# 1_PMIC_1.net
KiCad netlist of a schematic drawn in Altium Designer
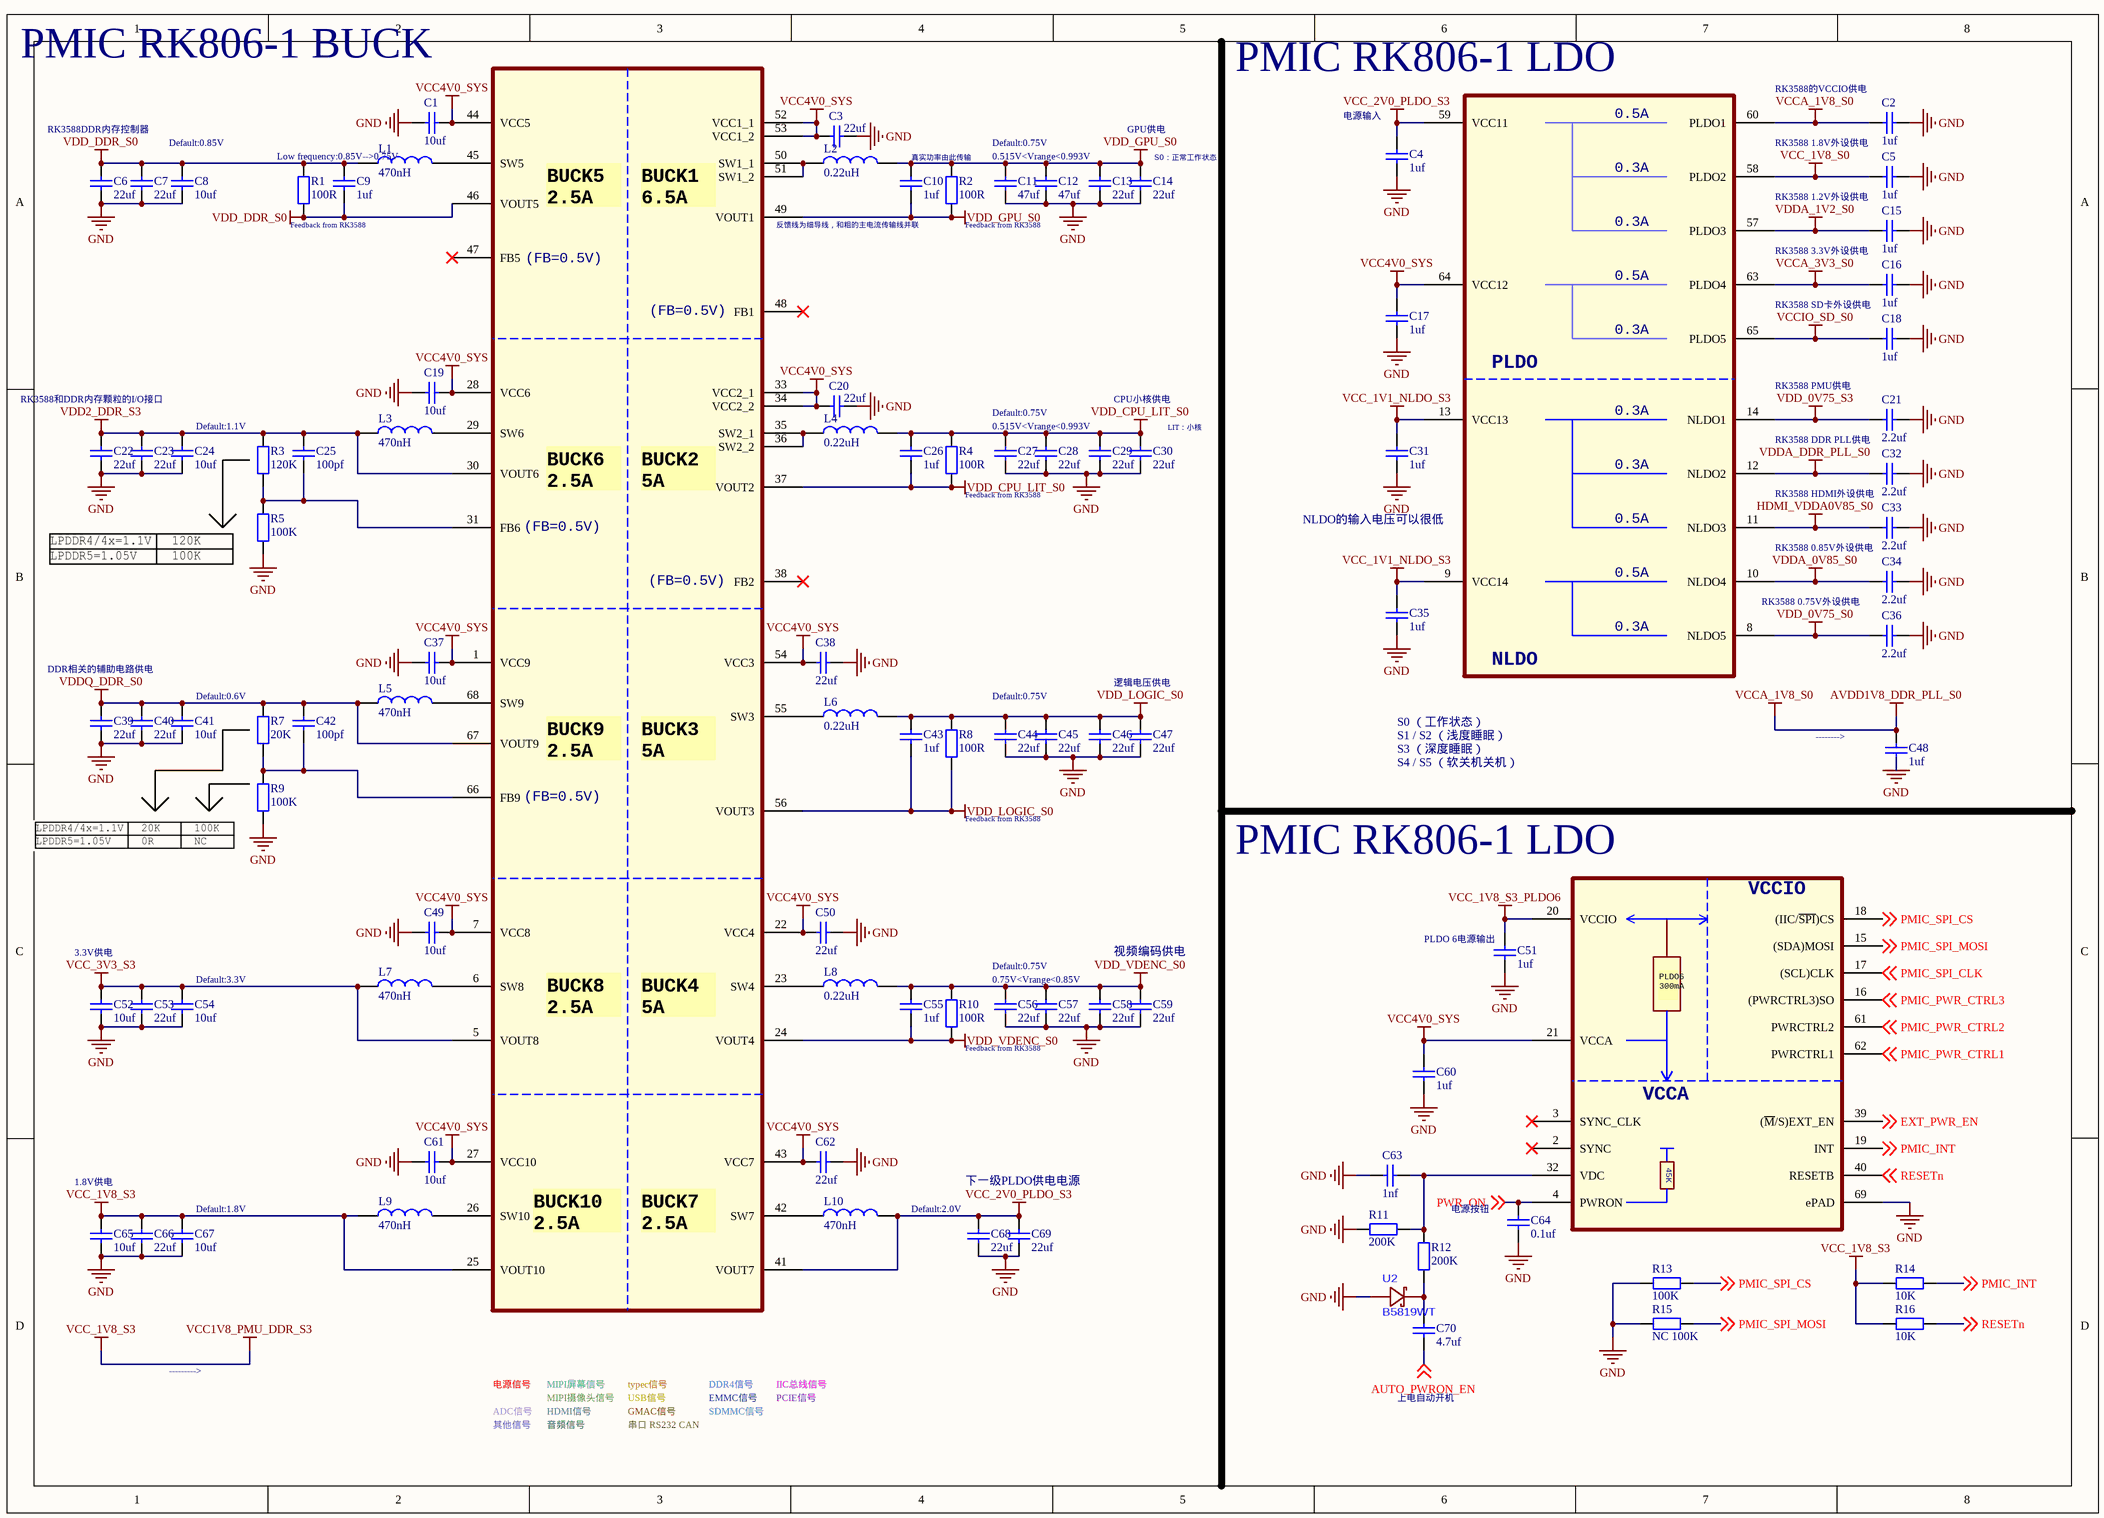
[diagram p0: 1.PMIC_1.SchDoc]

(export (version "E")
  (design (tool "Eeschema 10.0.6"))
  (components
    (comp (ref "C1")
      (value "10uf")
      (footprint "0.PCB1:C0603_L")
      (description "贴片电容/MLCC电容")
      (libsource (lib "RK3588") (part "C"))
    )
    (comp (ref "C2")
      (value "1uf")
      (footprint "0.PCB1:C0402_L")
      (description "贴片电容/MLCC电容")
      (libsource (lib "RK3588") (part "C"))
    )
    (comp (ref "C3")
      (value "22uf")
      (footprint "0.PCB1:C0603_L")
      (description "贴片电容/MLCC电容")
      (libsource (lib "RK3588") (part "C"))
    )
    (comp (ref "C4")
      (value "1uf")
      (footprint "0.PCB1:C0402_L")
      (description "贴片电容/MLCC电容")
      (libsource (lib "RK3588") (part "C"))
    )
    (comp (ref "C5")
      (value "1uf")
      (footprint "0.PCB1:C0402_L")
      (description "贴片电容/MLCC电容")
      (libsource (lib "RK3588") (part "C"))
    )
    (comp (ref "C6")
      (value "22uf")
      (footprint "0.PCB1:C0603_L")
      (description "贴片电容/MLCC电容")
      (libsource (lib "RK3588") (part "C"))
    )
    (comp (ref "C7")
      (value "22uf")
      (footprint "0.PCB1:C0603_L")
      (description "贴片电容/MLCC电容")
      (libsource (lib "RK3588") (part "C"))
    )
    (comp (ref "C8")
      (value "10uf")
      (footprint "0.PCB1:C0402_L")
      (description "贴片电容/MLCC电容")
      (libsource (lib "RK3588") (part "C"))
    )
    (comp (ref "C9")
      (value "1uf")
      (footprint "0.PCB1:C0402_L")
      (description "贴片电容/MLCC电容")
      (libsource (lib "RK3588") (part "C"))
    )
    (comp (ref "C10")
      (value "1uf")
      (footprint "0.PCB1:C0402_L")
      (description "贴片电容/MLCC电容")
      (libsource (lib "RK3588") (part "C"))
    )
    (comp (ref "C11")
      (value "47uf")
      (footprint "0.PCB1:C0805_L")
      (description "贴片电容/MLCC电容")
      (libsource (lib "RK3588") (part "C"))
    )
    (comp (ref "C12")
      (value "47uf")
      (footprint "0.PCB1:C0805_L")
      (description "贴片电容/MLCC电容")
      (libsource (lib "RK3588") (part "C"))
    )
    (comp (ref "C13")
      (value "22uf")
      (footprint "0.PCB1:C0603_L")
      (description "贴片电容/MLCC电容")
      (libsource (lib "RK3588") (part "C"))
    )
    (comp (ref "C14")
      (value "22uf")
      (footprint "0.PCB1:C0603_L")
      (description "贴片电容/MLCC电容")
      (libsource (lib "RK3588") (part "C"))
    )
    (comp (ref "C15")
      (value "1uf")
      (footprint "0.PCB1:C0402_L")
      (description "贴片电容/MLCC电容")
      (libsource (lib "RK3588") (part "C"))
    )
    (comp (ref "C16")
      (value "1uf")
      (footprint "0.PCB1:C0402_L")
      (description "贴片电容/MLCC电容")
      (libsource (lib "RK3588") (part "C"))
    )
    (comp (ref "C17")
      (value "1uf")
      (footprint "0.PCB1:C0402_L")
      (description "贴片电容/MLCC电容")
      (libsource (lib "RK3588") (part "C"))
    )
    (comp (ref "C18")
      (value "1uf")
      (footprint "0.PCB1:C0402_L")
      (description "贴片电容/MLCC电容")
      (libsource (lib "RK3588") (part "C"))
    )
    (comp (ref "C19")
      (value "10uf")
      (footprint "0.PCB1:C0603_L")
      (description "贴片电容/MLCC电容")
      (libsource (lib "RK3588") (part "C"))
    )
    (comp (ref "C20")
      (value "22uf")
      (footprint "0.PCB1:C0603_L")
      (description "贴片电容/MLCC电容")
      (libsource (lib "RK3588") (part "C"))
    )
    (comp (ref "C21")
      (value "2.2uf")
      (footprint "0.PCB1:C0402_L")
      (description "贴片电容/MLCC电容")
      (libsource (lib "RK3588") (part "C"))
    )
    (comp (ref "C22")
      (value "22uf")
      (footprint "0.PCB1:C0603_L")
      (description "贴片电容/MLCC电容")
      (libsource (lib "RK3588") (part "C"))
    )
    (comp (ref "C23")
      (value "22uf")
      (footprint "0.PCB1:C0603_L")
      (description "贴片电容/MLCC电容")
      (libsource (lib "RK3588") (part "C"))
    )
    (comp (ref "C24")
      (value "10uf")
      (footprint "0.PCB1:C0402_L")
      (description "贴片电容/MLCC电容")
      (libsource (lib "RK3588") (part "C"))
    )
    (comp (ref "C25")
      (value "100pf")
      (footprint "0.PCB1:C0402_L")
      (description "贴片电容/MLCC电容")
      (libsource (lib "RK3588") (part "C"))
    )
    (comp (ref "C26")
      (value "1uf")
      (footprint "0.PCB1:C0402_L")
      (description "贴片电容/MLCC电容")
      (libsource (lib "RK3588") (part "C"))
    )
    (comp (ref "C27")
      (value "22uf")
      (footprint "0.PCB1:C0603_L")
      (description "贴片电容/MLCC电容")
      (libsource (lib "RK3588") (part "C"))
    )
    (comp (ref "C28")
      (value "22uf")
      (footprint "0.PCB1:C0603_L")
      (description "贴片电容/MLCC电容")
      (libsource (lib "RK3588") (part "C"))
    )
    (comp (ref "C29")
      (value "22uf")
      (footprint "0.PCB1:C0603_L")
      (description "贴片电容/MLCC电容")
      (libsource (lib "RK3588") (part "C"))
    )
    (comp (ref "C30")
      (value "22uf")
      (footprint "0.PCB1:C0603_L")
      (description "贴片电容/MLCC电容")
      (libsource (lib "RK3588") (part "C"))
    )
    (comp (ref "C31")
      (value "1uf")
      (footprint "0.PCB1:C0402_L")
      (description "贴片电容/MLCC电容")
      (libsource (lib "RK3588") (part "C"))
    )
    (comp (ref "C32")
      (value "2.2uf")
      (footprint "0.PCB1:C0402_L")
      (description "贴片电容/MLCC电容")
      (libsource (lib "RK3588") (part "C"))
    )
    (comp (ref "C33")
      (value "2.2uf")
      (footprint "0.PCB1:C0402_L")
      (description "贴片电容/MLCC电容")
      (libsource (lib "RK3588") (part "C"))
    )
    (comp (ref "C34")
      (value "2.2uf")
      (footprint "0.PCB1:C0402_L")
      (description "贴片电容/MLCC电容")
      (libsource (lib "RK3588") (part "C"))
    )
    (comp (ref "C35")
      (value "1uf")
      (footprint "0.PCB1:C0402_L")
      (description "贴片电容/MLCC电容")
      (libsource (lib "RK3588") (part "C"))
    )
    (comp (ref "C36")
      (value "2.2uf")
      (footprint "0.PCB1:C0402_L")
      (description "贴片电容/MLCC电容")
      (libsource (lib "RK3588") (part "C"))
    )
    (comp (ref "C37")
      (value "10uf")
      (footprint "0.PCB1:C0603_L")
      (description "贴片电容/MLCC电容")
      (libsource (lib "RK3588") (part "C"))
    )
    (comp (ref "C38")
      (value "22uf")
      (footprint "0.PCB1:C0603_L")
      (description "贴片电容/MLCC电容")
      (libsource (lib "RK3588") (part "C"))
    )
    (comp (ref "C39")
      (value "22uf")
      (footprint "0.PCB1:C0603_L")
      (description "贴片电容/MLCC电容")
      (libsource (lib "RK3588") (part "C"))
    )
    (comp (ref "C40")
      (value "22uf")
      (footprint "0.PCB1:C0603_L")
      (description "贴片电容/MLCC电容")
      (libsource (lib "RK3588") (part "C"))
    )
    (comp (ref "C41")
      (value "10uf")
      (footprint "0.PCB1:C0402_L")
      (description "贴片电容/MLCC电容")
      (libsource (lib "RK3588") (part "C"))
    )
    (comp (ref "C42")
      (value "100pf")
      (footprint "0.PCB1:C0402_L")
      (description "贴片电容/MLCC电容")
      (libsource (lib "RK3588") (part "C"))
    )
    (comp (ref "C43")
      (value "1uf")
      (footprint "0.PCB1:C0402_L")
      (description "贴片电容/MLCC电容")
      (libsource (lib "RK3588") (part "C"))
    )
    (comp (ref "C44")
      (value "22uf")
      (footprint "0.PCB1:C0805_L")
      (description "贴片电容/MLCC电容")
      (libsource (lib "RK3588") (part "C"))
    )
    (comp (ref "C45")
      (value "22uf")
      (footprint "0.PCB1:C0805_L")
      (description "贴片电容/MLCC电容")
      (libsource (lib "RK3588") (part "C"))
    )
    (comp (ref "C46")
      (value "22uf")
      (footprint "0.PCB1:C0603_L")
      (description "贴片电容/MLCC电容")
      (libsource (lib "RK3588") (part "C"))
    )
    (comp (ref "C47")
      (value "22uf")
      (footprint "0.PCB1:C0603_L")
      (description "贴片电容/MLCC电容")
      (libsource (lib "RK3588") (part "C"))
    )
    (comp (ref "C48")
      (value "1uf")
      (footprint "0.PCB1:C0402_L")
      (description "贴片电容/MLCC电容")
      (libsource (lib "RK3588") (part "C"))
    )
    (comp (ref "C49")
      (value "10uf")
      (footprint "0.PCB1:C0603_L")
      (description "贴片电容/MLCC电容")
      (libsource (lib "RK3588") (part "C"))
    )
    (comp (ref "C50")
      (value "22uf")
      (footprint "0.PCB1:C0603_L")
      (description "贴片电容/MLCC电容")
      (libsource (lib "RK3588") (part "C"))
    )
    (comp (ref "C51")
      (value "1uf")
      (footprint "0.PCB1:C0402_L")
      (description "贴片电容/MLCC电容")
      (libsource (lib "RK3588") (part "C"))
    )
    (comp (ref "C52")
      (value "10uf")
      (footprint "0.PCB1:C0603_L")
      (description "贴片电容/MLCC电容")
      (libsource (lib "RK3588") (part "C"))
    )
    (comp (ref "C53")
      (value "22uf")
      (footprint "0.PCB1:C0603_L")
      (description "贴片电容/MLCC电容")
      (libsource (lib "RK3588") (part "C"))
    )
    (comp (ref "C54")
      (value "10uf")
      (footprint "0.PCB1:C0402_L")
      (description "贴片电容/MLCC电容")
      (libsource (lib "RK3588") (part "C"))
    )
    (comp (ref "C55")
      (value "1uf")
      (footprint "0.PCB1:C0402_L")
      (description "贴片电容/MLCC电容")
      (libsource (lib "RK3588") (part "C"))
    )
    (comp (ref "C56")
      (value "22uf")
      (footprint "0.PCB1:C0805_L")
      (description "贴片电容/MLCC电容")
      (libsource (lib "RK3588") (part "C"))
    )
    (comp (ref "C57")
      (value "22uf")
      (footprint "0.PCB1:C0805_L")
      (description "贴片电容/MLCC电容")
      (libsource (lib "RK3588") (part "C"))
    )
    (comp (ref "C58")
      (value "22uf")
      (footprint "0.PCB1:C0603_L")
      (description "贴片电容/MLCC电容")
      (libsource (lib "RK3588") (part "C"))
    )
    (comp (ref "C59")
      (value "22uf")
      (footprint "0.PCB1:C0603_L")
      (description "贴片电容/MLCC电容")
      (libsource (lib "RK3588") (part "C"))
    )
    (comp (ref "C60")
      (value "1uf")
      (footprint "0.PCB1:C0402_L")
      (description "贴片电容/MLCC电容")
      (libsource (lib "RK3588") (part "C"))
    )
    (comp (ref "C61")
      (value "10uf")
      (footprint "0.PCB1:C0603_L")
      (description "贴片电容/MLCC电容")
      (libsource (lib "RK3588") (part "C"))
    )
    (comp (ref "C62")
      (value "22uf")
      (footprint "0.PCB1:C0603_L")
      (description "贴片电容/MLCC电容")
      (libsource (lib "RK3588") (part "C"))
    )
    (comp (ref "C63")
      (value "1nf")
      (footprint "0.PCB1:C0402_L")
      (description "贴片电容/MLCC电容")
      (libsource (lib "RK3588") (part "C"))
    )
    (comp (ref "C64")
      (value "0.1uf")
      (footprint "0.PCB1:C0402_L")
      (description "贴片电容/MLCC电容")
      (libsource (lib "RK3588") (part "C"))
    )
    (comp (ref "C65")
      (value "10uf")
      (footprint "0.PCB1:C0603_L")
      (description "贴片电容/MLCC电容")
      (libsource (lib "RK3588") (part "C"))
    )
    (comp (ref "C66")
      (value "22uf")
      (footprint "0.PCB1:C0603_L")
      (description "贴片电容/MLCC电容")
      (libsource (lib "RK3588") (part "C"))
    )
    (comp (ref "C67")
      (value "10uf")
      (footprint "0.PCB1:C0402_L")
      (description "贴片电容/MLCC电容")
      (libsource (lib "RK3588") (part "C"))
    )
    (comp (ref "C68")
      (value "22uf")
      (footprint "0.PCB1:C0603_L")
      (description "贴片电容/MLCC电容")
      (libsource (lib "RK3588") (part "C"))
    )
    (comp (ref "C69")
      (value "22uf")
      (footprint "0.PCB1:C0603_L")
      (description "贴片电容/MLCC电容")
      (libsource (lib "RK3588") (part "C"))
    )
    (comp (ref "C70")
      (value "4.7uf")
      (footprint "0.PCB1:C0402_L")
      (description "贴片电容/MLCC电容")
      (libsource (lib "RK3588") (part "C"))
    )
    (comp (ref "L1")
      (value "470nH")
      (footprint "0.PCB1:L0805")
      (description "贴片小功率电感")
      (libsource (lib "RK3588") (part "L"))
    )
    (comp (ref "L2")
      (value "0.22uH")
      (footprint "0.PCB1:L0805")
      (description "贴片小功率电感")
      (libsource (lib "") (part "L_1"))
    )
    (comp (ref "L3")
      (value "470nH")
      (footprint "0.PCB1:L0805")
      (description "贴片小功率电感")
      (libsource (lib "RK3588") (part "L"))
    )
    (comp (ref "L4")
      (value "0.22uH")
      (footprint "0.PCB1:L0805")
      (description "贴片小功率电感")
      (libsource (lib "") (part "L_1"))
    )
    (comp (ref "L5")
      (value "470nH")
      (footprint "0.PCB1:L0805")
      (description "贴片小功率电感")
      (libsource (lib "RK3588") (part "L"))
    )
    (comp (ref "L6")
      (value "0.22uH")
      (footprint "0.PCB1:L0805")
      (description "贴片小功率电感")
      (libsource (lib "") (part "L_1"))
    )
    (comp (ref "L7")
      (value "470nH")
      (footprint "0.PCB1:L0805")
      (description "贴片小功率电感")
      (libsource (lib "RK3588") (part "L"))
    )
    (comp (ref "L8")
      (value "0.22uH")
      (footprint "0.PCB1:L0805")
      (description "贴片小功率电感")
      (libsource (lib "") (part "L_1"))
    )
    (comp (ref "L9")
      (value "470nH")
      (footprint "0.PCB1:L0805")
      (description "贴片小功率电感")
      (libsource (lib "RK3588") (part "L"))
    )
    (comp (ref "L10")
      (value "470nH")
      (footprint "0.PCB1:L0805")
      (description "贴片小功率电感")
      (libsource (lib "") (part "L_1"))
    )
    (comp (ref "R1")
      (value "100R")
      (footprint "0.PCB1:R0402_L")
      (description "贴片电阻")
      (libsource (lib "RK3588") (part "R"))
    )
    (comp (ref "R2")
      (value "100R")
      (footprint "0.PCB1:R0402_L")
      (description "贴片电阻")
      (libsource (lib "RK3588") (part "R"))
    )
    (comp (ref "R3")
      (value "120K")
      (footprint "0.PCB1:R0402_L")
      (description "贴片电阻")
      (libsource (lib "RK3588") (part "R"))
    )
    (comp (ref "R4")
      (value "100R")
      (footprint "0.PCB1:R0402_L")
      (description "贴片电阻")
      (libsource (lib "RK3588") (part "R"))
    )
    (comp (ref "R5")
      (value "100K")
      (footprint "0.PCB1:R0402_L")
      (description "贴片电阻")
      (libsource (lib "RK3588") (part "R"))
    )
    (comp (ref "R7")
      (value "20K")
      (footprint "0.PCB1:R0402_L")
      (description "贴片电阻")
      (libsource (lib "RK3588") (part "R"))
    )
    (comp (ref "R8")
      (value "100R")
      (footprint "0.PCB1:R0402_L")
      (description "贴片电阻")
      (libsource (lib "RK3588") (part "R"))
    )
    (comp (ref "R9")
      (value "100K")
      (footprint "0.PCB1:R0402_L")
      (description "贴片电阻")
      (libsource (lib "RK3588") (part "R"))
    )
    (comp (ref "R10")
      (value "100R")
      (footprint "0.PCB1:R0402_L")
      (description "贴片电阻")
      (libsource (lib "RK3588") (part "R"))
    )
    (comp (ref "R11")
      (value "200K")
      (footprint "0.PCB1:R0402_L")
      (description "贴片电阻")
      (libsource (lib "RK3588") (part "R"))
    )
    (comp (ref "R12")
      (value "200K")
      (footprint "0.PCB1:R0402_L")
      (description "贴片电阻")
      (libsource (lib "RK3588") (part "R"))
    )
    (comp (ref "R13")
      (value "100K")
      (footprint "0.PCB1:R0402_L")
      (description "贴片电阻")
      (libsource (lib "RK3588") (part "R"))
    )
    (comp (ref "R14")
      (value "10K")
      (footprint "0.PCB1:R0402_L")
      (description "贴片电阻")
      (libsource (lib "RK3588") (part "R"))
    )
    (comp (ref "R15")
      (value "NC 100K")
      (footprint "0.PCB1:R0402_L")
      (description "贴片电阻")
      (libsource (lib "RK3588") (part "R"))
    )
    (comp (ref "R16")
      (value "10K")
      (footprint "0.PCB1:R0402_L")
      (description "贴片电阻")
      (libsource (lib "RK3588") (part "R"))
    )
    (comp (ref "U1")
      (value "PMIC_RK806")
      (footprint "0.PCB1:QFN68_7R00X7R00X0R80_T")
      (libsource (lib "RK3588") (part "PMIC_RK806"))
    )
    (comp (ref "U2")
      (value "B5819WT")
      (footprint "0.PCB1:SOD-523_L1.2-W0.8-LS1.6-RD")
      (libsource (lib "RK3588") (part "B5819WT"))
    )
  )
  (nets
    (net (code "1") (name "AUTO_PWRON_EN") (class "Default")
      (node (ref "C70") (pin "2") (pinfunction "2_2") (pintype "passive"))
    )
    (net (code "2") (name "AVDD1V8_DDR_PLL_S0") (class "Default")
      (node (ref "C2") (pin "2") (pinfunction "2_2") (pintype "passive"))
      (node (ref "C48") (pin "1") (pinfunction "1_1") (pintype "passive"))
      (node (ref "U1") (pin "60") (pinfunction "PLDO1_60") (pintype "passive"))
    )
    (net (code "3") (name "EXT_PWR_EN") (class "Default")
      (node (ref "U1") (pin "39") (pinfunction "(~{M}/S)EXT_EN_39") (pintype "passive"))
    )
    (net (code "4") (name "GND") (class "Default")
      (node (ref "C1") (pin "2") (pinfunction "2_2") (pintype "passive"))
      (node (ref "C11") (pin "1") (pinfunction "1_1") (pintype "passive"))
      (node (ref "C12") (pin "1") (pinfunction "1_1") (pintype "passive"))
      (node (ref "C13") (pin "1") (pinfunction "1_1") (pintype "passive"))
      (node (ref "C14") (pin "1") (pinfunction "1_1") (pintype "passive"))
      (node (ref "C15") (pin "1") (pinfunction "1_1") (pintype "passive"))
      (node (ref "C16") (pin "1") (pinfunction "1_1") (pintype "passive"))
      (node (ref "C17") (pin "1") (pinfunction "1_1") (pintype "passive"))
      (node (ref "C18") (pin "1") (pinfunction "1_1") (pintype "passive"))
      (node (ref "C19") (pin "2") (pinfunction "2_2") (pintype "passive"))
      (node (ref "C2") (pin "1") (pinfunction "1_1") (pintype "passive"))
      (node (ref "C20") (pin "2") (pinfunction "2_2") (pintype "passive"))
      (node (ref "C21") (pin "1") (pinfunction "1_1") (pintype "passive"))
      (node (ref "C22") (pin "1") (pinfunction "1_1") (pintype "passive"))
      (node (ref "C23") (pin "1") (pinfunction "1_1") (pintype "passive"))
      (node (ref "C24") (pin "1") (pinfunction "1_1") (pintype "passive"))
      (node (ref "C27") (pin "1") (pinfunction "1_1") (pintype "passive"))
      (node (ref "C28") (pin "1") (pinfunction "1_1") (pintype "passive"))
      (node (ref "C29") (pin "1") (pinfunction "1_1") (pintype "passive"))
      (node (ref "C3") (pin "2") (pinfunction "2_2") (pintype "passive"))
      (node (ref "C30") (pin "1") (pinfunction "1_1") (pintype "passive"))
      (node (ref "C31") (pin "1") (pinfunction "1_1") (pintype "passive"))
      (node (ref "C32") (pin "1") (pinfunction "1_1") (pintype "passive"))
      (node (ref "C33") (pin "1") (pinfunction "1_1") (pintype "passive"))
      (node (ref "C34") (pin "1") (pinfunction "1_1") (pintype "passive"))
      (node (ref "C35") (pin "1") (pinfunction "1_1") (pintype "passive"))
      (node (ref "C36") (pin "1") (pinfunction "1_1") (pintype "passive"))
      (node (ref "C37") (pin "2") (pinfunction "2_2") (pintype "passive"))
      (node (ref "C38") (pin "2") (pinfunction "2_2") (pintype "passive"))
      (node (ref "C39") (pin "1") (pinfunction "1_1") (pintype "passive"))
      (node (ref "C4") (pin "1") (pinfunction "1_1") (pintype "passive"))
      (node (ref "C40") (pin "1") (pinfunction "1_1") (pintype "passive"))
      (node (ref "C41") (pin "1") (pinfunction "1_1") (pintype "passive"))
      (node (ref "C44") (pin "1") (pinfunction "1_1") (pintype "passive"))
      (node (ref "C45") (pin "1") (pinfunction "1_1") (pintype "passive"))
      (node (ref "C46") (pin "1") (pinfunction "1_1") (pintype "passive"))
      (node (ref "C47") (pin "1") (pinfunction "1_1") (pintype "passive"))
      (node (ref "C48") (pin "2") (pinfunction "2_2") (pintype "passive"))
      (node (ref "C49") (pin "2") (pinfunction "2_2") (pintype "passive"))
      (node (ref "C5") (pin "1") (pinfunction "1_1") (pintype "passive"))
      (node (ref "C50") (pin "2") (pinfunction "2_2") (pintype "passive"))
      (node (ref "C51") (pin "1") (pinfunction "1_1") (pintype "passive"))
      (node (ref "C52") (pin "1") (pinfunction "1_1") (pintype "passive"))
      (node (ref "C53") (pin "1") (pinfunction "1_1") (pintype "passive"))
      (node (ref "C54") (pin "1") (pinfunction "1_1") (pintype "passive"))
      (node (ref "C56") (pin "1") (pinfunction "1_1") (pintype "passive"))
      (node (ref "C57") (pin "1") (pinfunction "1_1") (pintype "passive"))
      (node (ref "C58") (pin "1") (pinfunction "1_1") (pintype "passive"))
      (node (ref "C59") (pin "1") (pinfunction "1_1") (pintype "passive"))
      (node (ref "C6") (pin "1") (pinfunction "1_1") (pintype "passive"))
      (node (ref "C60") (pin "1") (pinfunction "1_1") (pintype "passive"))
      (node (ref "C61") (pin "2") (pinfunction "2_2") (pintype "passive"))
      (node (ref "C62") (pin "2") (pinfunction "2_2") (pintype "passive"))
      (node (ref "C63") (pin "1") (pinfunction "1_1") (pintype "passive"))
      (node (ref "C64") (pin "1") (pinfunction "1_1") (pintype "passive"))
      (node (ref "C65") (pin "1") (pinfunction "1_1") (pintype "passive"))
      (node (ref "C66") (pin "1") (pinfunction "1_1") (pintype "passive"))
      (node (ref "C67") (pin "1") (pinfunction "1_1") (pintype "passive"))
      (node (ref "C68") (pin "1") (pinfunction "1_1") (pintype "passive"))
      (node (ref "C69") (pin "1") (pinfunction "1_1") (pintype "passive"))
      (node (ref "C7") (pin "1") (pinfunction "1_1") (pintype "passive"))
      (node (ref "C8") (pin "1") (pinfunction "1_1") (pintype "passive"))
      (node (ref "R11") (pin "1") (pinfunction "1_1") (pintype "passive"))
      (node (ref "R13") (pin "1") (pinfunction "1_1") (pintype "passive"))
      (node (ref "R15") (pin "1") (pinfunction "1_1") (pintype "passive"))
      (node (ref "R5") (pin "1") (pinfunction "1_1") (pintype "passive"))
      (node (ref "R9") (pin "1") (pinfunction "1_1") (pintype "passive"))
      (node (ref "U1") (pin "69") (pinfunction "ePAD_69") (pintype "passive"))
      (node (ref "U2") (pin "2") (pinfunction "A_2") (pintype "passive"))
    )
    (net (code "5") (name "HDMI_VDDA0V85_S0") (class "Default")
      (node (ref "C33") (pin "2") (pinfunction "2_2") (pintype "passive"))
      (node (ref "U1") (pin "11") (pinfunction "NLDO3_11") (pintype "passive"))
    )
    (net (code "6") (name "Net-(U1A-FB6)") (class "Default")
      (node (ref "C25") (pin "1") (pinfunction "1_1") (pintype "passive"))
      (node (ref "R3") (pin "1") (pinfunction "1_1") (pintype "passive"))
      (node (ref "R5") (pin "2") (pinfunction "2_2") (pintype "passive"))
      (node (ref "U1") (pin "31") (pinfunction "FB6_31") (pintype "passive"))
    )
    (net (code "7") (name "Net-(U1A-FB9)") (class "Default")
      (node (ref "C42") (pin "1") (pinfunction "1_1") (pintype "passive"))
      (node (ref "R7") (pin "1") (pinfunction "1_1") (pintype "passive"))
      (node (ref "R9") (pin "2") (pinfunction "2_2") (pintype "passive"))
      (node (ref "U1") (pin "66") (pinfunction "FB9_66") (pintype "passive"))
    )
    (net (code "8") (name "Net-(U1A-SW1_1)") (class "Default")
      (node (ref "L2") (pin "1") (pinfunction "1_1") (pintype "passive"))
      (node (ref "U1") (pin "50") (pinfunction "SW1_1_50") (pintype "passive"))
      (node (ref "U1") (pin "51") (pinfunction "SW1_2_51") (pintype "passive"))
    )
    (net (code "9") (name "Net-(U1A-SW2_1)") (class "Default")
      (node (ref "L4") (pin "1") (pinfunction "1_1") (pintype "passive"))
      (node (ref "U1") (pin "35") (pinfunction "SW2_1_35") (pintype "passive"))
      (node (ref "U1") (pin "36") (pinfunction "SW2_2_36") (pintype "passive"))
    )
    (net (code "10") (name "Net-(U1A-SW3)") (class "Default")
      (node (ref "L6") (pin "1") (pinfunction "1_1") (pintype "passive"))
      (node (ref "U1") (pin "55") (pinfunction "SW3_55") (pintype "passive"))
    )
    (net (code "11") (name "Net-(U1A-SW4)") (class "Default")
      (node (ref "L8") (pin "1") (pinfunction "1_1") (pintype "passive"))
      (node (ref "U1") (pin "23") (pinfunction "SW4_23") (pintype "passive"))
    )
    (net (code "12") (name "Net-(U1A-SW5)") (class "Default")
      (node (ref "L1") (pin "1") (pinfunction "1_1") (pintype "passive"))
      (node (ref "U1") (pin "45") (pinfunction "SW5_45") (pintype "passive"))
    )
    (net (code "13") (name "Net-(U1A-SW6)") (class "Default")
      (node (ref "L3") (pin "1") (pinfunction "1_1") (pintype "passive"))
      (node (ref "U1") (pin "29") (pinfunction "SW6_29") (pintype "passive"))
    )
    (net (code "14") (name "Net-(U1A-SW7)") (class "Default")
      (node (ref "L10") (pin "1") (pinfunction "1_1") (pintype "passive"))
      (node (ref "U1") (pin "42") (pinfunction "SW7_42") (pintype "passive"))
    )
    (net (code "15") (name "Net-(U1A-SW8)") (class "Default")
      (node (ref "L7") (pin "1") (pinfunction "1_1") (pintype "passive"))
      (node (ref "U1") (pin "6") (pinfunction "SW8_6") (pintype "passive"))
    )
    (net (code "16") (name "Net-(U1A-SW9)") (class "Default")
      (node (ref "L5") (pin "1") (pinfunction "1_1") (pintype "passive"))
      (node (ref "U1") (pin "68") (pinfunction "SW9_68") (pintype "passive"))
    )
    (net (code "17") (name "Net-(U1A-SW10)") (class "Default")
      (node (ref "L9") (pin "1") (pinfunction "1_1") (pintype "passive"))
      (node (ref "U1") (pin "26") (pinfunction "SW10_26") (pintype "passive"))
    )
    (net (code "18") (name "Net-(U1C-VDC)") (class "Default")
      (node (ref "C63") (pin "2") (pinfunction "2_2") (pintype "passive"))
      (node (ref "R11") (pin "2") (pinfunction "2_2") (pintype "passive"))
      (node (ref "R12") (pin "2") (pinfunction "2_2") (pintype "passive"))
      (node (ref "U1") (pin "32") (pinfunction "VDC_32") (pintype "passive"))
    )
    (net (code "19") (name "Net-(U2-C)") (class "Default")
      (node (ref "C70") (pin "1") (pinfunction "1_1") (pintype "passive"))
      (node (ref "R12") (pin "1") (pinfunction "1_1") (pintype "passive"))
      (node (ref "U2") (pin "1") (pinfunction "C_1") (pintype "passive"))
    )
    (net (code "20") (name "PMIC_INT") (class "Default")
      (node (ref "R14") (pin "2") (pinfunction "2_2") (pintype "passive"))
      (node (ref "U1") (pin "19") (pinfunction "INT_19") (pintype "passive"))
    )
    (net (code "21") (name "PMIC_PWR_CTRL1") (class "Default")
      (node (ref "U1") (pin "62") (pinfunction "PWRCTRL1_62") (pintype "passive"))
    )
    (net (code "22") (name "PMIC_PWR_CTRL2") (class "Default")
      (node (ref "U1") (pin "61") (pinfunction "PWRCTRL2_61") (pintype "passive"))
    )
    (net (code "23") (name "PMIC_PWR_CTRL3") (class "Default")
      (node (ref "U1") (pin "16") (pinfunction "(PWRCTRL3)SO_16") (pintype "passive"))
    )
    (net (code "24") (name "PMIC_SPI_CLK") (class "Default")
      (node (ref "U1") (pin "17") (pinfunction "(SCL)CLK_17") (pintype "passive"))
    )
    (net (code "25") (name "PMIC_SPI_CS") (class "Default")
      (node (ref "R13") (pin "2") (pinfunction "2_2") (pintype "passive"))
      (node (ref "U1") (pin "18") (pinfunction "(IIC/~{SPI})CS_18") (pintype "passive"))
    )
    (net (code "26") (name "PMIC_SPI_MOSI") (class "Default")
      (node (ref "R15") (pin "2") (pinfunction "2_2") (pintype "passive"))
      (node (ref "U1") (pin "15") (pinfunction "(SDA)MOSI_15") (pintype "passive"))
    )
    (net (code "27") (name "PWR_ON") (class "Default")
      (node (ref "C64") (pin "2") (pinfunction "2_2") (pintype "passive"))
      (node (ref "U1") (pin "4") (pinfunction "PWRON_4") (pintype "passive"))
    )
    (net (code "28") (name "RESETn") (class "Default")
      (node (ref "R16") (pin "2") (pinfunction "2_2") (pintype "passive"))
      (node (ref "U1") (pin "40") (pinfunction "RESETB_40") (pintype "passive"))
    )
    (net (code "29") (name "VCC1V8_PMU_DDR_S3") (class "Default")
      (node (ref "C65") (pin "2") (pinfunction "2_2") (pintype "passive"))
      (node (ref "C66") (pin "2") (pinfunction "2_2") (pintype "passive"))
      (node (ref "C67") (pin "2") (pinfunction "2_2") (pintype "passive"))
      (node (ref "L9") (pin "2") (pinfunction "2_2") (pintype "passive"))
      (node (ref "R14") (pin "1") (pinfunction "1_1") (pintype "passive"))
      (node (ref "R16") (pin "1") (pinfunction "1_1") (pintype "passive"))
      (node (ref "U1") (pin "25") (pinfunction "VOUT10_25") (pintype "passive"))
    )
    (net (code "30") (name "VCC4V0_SYS") (class "Default")
      (node (ref "C1") (pin "1") (pinfunction "1_1") (pintype "passive"))
      (node (ref "C17") (pin "2") (pinfunction "2_2") (pintype "passive"))
      (node (ref "C19") (pin "1") (pinfunction "1_1") (pintype "passive"))
      (node (ref "C20") (pin "1") (pinfunction "1_1") (pintype "passive"))
      (node (ref "C3") (pin "1") (pinfunction "1_1") (pintype "passive"))
      (node (ref "C37") (pin "1") (pinfunction "1_1") (pintype "passive"))
      (node (ref "C38") (pin "1") (pinfunction "1_1") (pintype "passive"))
      (node (ref "C49") (pin "1") (pinfunction "1_1") (pintype "passive"))
      (node (ref "C50") (pin "1") (pinfunction "1_1") (pintype "passive"))
      (node (ref "C60") (pin "2") (pinfunction "2_2") (pintype "passive"))
      (node (ref "C61") (pin "1") (pinfunction "1_1") (pintype "passive"))
      (node (ref "C62") (pin "1") (pinfunction "1_1") (pintype "passive"))
      (node (ref "U1") (pin "1") (pinfunction "VCC9_1") (pintype "passive"))
      (node (ref "U1") (pin "21") (pinfunction "VCCA_21") (pintype "passive"))
      (node (ref "U1") (pin "22") (pinfunction "VCC4_22") (pintype "passive"))
      (node (ref "U1") (pin "27") (pinfunction "VCC10_27") (pintype "passive"))
      (node (ref "U1") (pin "28") (pinfunction "VCC6_28") (pintype "passive"))
      (node (ref "U1") (pin "33") (pinfunction "VCC2_1_33") (pintype "passive"))
      (node (ref "U1") (pin "34") (pinfunction "VCC2_2_34") (pintype "passive"))
      (node (ref "U1") (pin "43") (pinfunction "VCC7_43") (pintype "passive"))
      (node (ref "U1") (pin "44") (pinfunction "VCC5_44") (pintype "passive"))
      (node (ref "U1") (pin "52") (pinfunction "VCC1_1_52") (pintype "passive"))
      (node (ref "U1") (pin "53") (pinfunction "VCC1_2_53") (pintype "passive"))
      (node (ref "U1") (pin "54") (pinfunction "VCC3_54") (pintype "passive"))
      (node (ref "U1") (pin "64") (pinfunction "VCC12_64") (pintype "passive"))
      (node (ref "U1") (pin "7") (pinfunction "VCC8_7") (pintype "passive"))
    )
    (net (code "31") (name "VCCA_3V3_S0") (class "Default")
      (node (ref "C16") (pin "2") (pinfunction "2_2") (pintype "passive"))
      (node (ref "U1") (pin "63") (pinfunction "PLDO4_63") (pintype "passive"))
    )
    (net (code "32") (name "VCCIO_SD_S0") (class "Default")
      (node (ref "C18") (pin "2") (pinfunction "2_2") (pintype "passive"))
      (node (ref "U1") (pin "65") (pinfunction "PLDO5_65") (pintype "passive"))
    )
    (net (code "33") (name "VCC_1V1_NLDO_S3") (class "Default")
      (node (ref "C31") (pin "2") (pinfunction "2_2") (pintype "passive"))
      (node (ref "C35") (pin "2") (pinfunction "2_2") (pintype "passive"))
      (node (ref "U1") (pin "13") (pinfunction "VCC13_13") (pintype "passive"))
      (node (ref "U1") (pin "9") (pinfunction "VCC14_9") (pintype "passive"))
    )
    (net (code "34") (name "VCC_1V8_S0") (class "Default")
      (node (ref "C5") (pin "2") (pinfunction "2_2") (pintype "passive"))
      (node (ref "U1") (pin "58") (pinfunction "PLDO2_58") (pintype "passive"))
    )
    (net (code "35") (name "VCC_1V8_S3_PLDO6") (class "Default")
      (node (ref "C51") (pin "2") (pinfunction "2_2") (pintype "passive"))
      (node (ref "U1") (pin "20") (pinfunction "VCCIO_20") (pintype "passive"))
    )
    (net (code "36") (name "VCC_2V0_PLDO_S3") (class "Default")
      (node (ref "C4") (pin "2") (pinfunction "2_2") (pintype "passive"))
      (node (ref "C68") (pin "2") (pinfunction "2_2") (pintype "passive"))
      (node (ref "C69") (pin "2") (pinfunction "2_2") (pintype "passive"))
      (node (ref "L10") (pin "2") (pinfunction "2_2") (pintype "passive"))
      (node (ref "U1") (pin "41") (pinfunction "VOUT7_41") (pintype "passive"))
      (node (ref "U1") (pin "59") (pinfunction "VCC11_59") (pintype "passive"))
    )
    (net (code "37") (name "VCC_3V3_S3") (class "Default")
      (node (ref "C52") (pin "2") (pinfunction "2_2") (pintype "passive"))
      (node (ref "C53") (pin "2") (pinfunction "2_2") (pintype "passive"))
      (node (ref "C54") (pin "2") (pinfunction "2_2") (pintype "passive"))
      (node (ref "L7") (pin "2") (pinfunction "2_2") (pintype "passive"))
      (node (ref "U1") (pin "5") (pinfunction "VOUT8_5") (pintype "passive"))
    )
    (net (code "38") (name "VDD2_DDR_S3") (class "Default")
      (node (ref "C22") (pin "2") (pinfunction "2_2") (pintype "passive"))
      (node (ref "C23") (pin "2") (pinfunction "2_2") (pintype "passive"))
      (node (ref "C24") (pin "2") (pinfunction "2_2") (pintype "passive"))
      (node (ref "C25") (pin "2") (pinfunction "2_2") (pintype "passive"))
      (node (ref "L3") (pin "2") (pinfunction "2_2") (pintype "passive"))
      (node (ref "R3") (pin "2") (pinfunction "2_2") (pintype "passive"))
      (node (ref "U1") (pin "30") (pinfunction "VOUT6_30") (pintype "passive"))
    )
    (net (code "39") (name "VDDA_0V85_S0") (class "Default")
      (node (ref "C34") (pin "2") (pinfunction "2_2") (pintype "passive"))
      (node (ref "U1") (pin "10") (pinfunction "NLDO4_10") (pintype "passive"))
    )
    (net (code "40") (name "VDDA_1V2_S0") (class "Default")
      (node (ref "C15") (pin "2") (pinfunction "2_2") (pintype "passive"))
      (node (ref "U1") (pin "57") (pinfunction "PLDO3_57") (pintype "passive"))
    )
    (net (code "41") (name "VDDA_DDR_PLL_S0") (class "Default")
      (node (ref "C32") (pin "2") (pinfunction "2_2") (pintype "passive"))
      (node (ref "U1") (pin "12") (pinfunction "NLDO2_12") (pintype "passive"))
    )
    (net (code "42") (name "VDDQ_DDR_S0") (class "Default")
      (node (ref "C39") (pin "2") (pinfunction "2_2") (pintype "passive"))
      (node (ref "C40") (pin "2") (pinfunction "2_2") (pintype "passive"))
      (node (ref "C41") (pin "2") (pinfunction "2_2") (pintype "passive"))
      (node (ref "C42") (pin "2") (pinfunction "2_2") (pintype "passive"))
      (node (ref "L5") (pin "2") (pinfunction "2_2") (pintype "passive"))
      (node (ref "R7") (pin "2") (pinfunction "2_2") (pintype "passive"))
      (node (ref "U1") (pin "67") (pinfunction "VOUT9_67") (pintype "passive"))
    )
    (net (code "43") (name "VDD_0V75_S0") (class "Default")
      (node (ref "C36") (pin "2") (pinfunction "2_2") (pintype "passive"))
      (node (ref "U1") (pin "8") (pinfunction "NLDO5_8") (pintype "passive"))
    )
    (net (code "44") (name "VDD_0V75_S3") (class "Default")
      (node (ref "C21") (pin "2") (pinfunction "2_2") (pintype "passive"))
      (node (ref "U1") (pin "14") (pinfunction "NLDO1_14") (pintype "passive"))
    )
    (net (code "45") (name "VDD_CPU_LIT_S0") (class "Default")
      (node (ref "C26") (pin "1") (pinfunction "1_1") (pintype "passive"))
      (node (ref "C26") (pin "2") (pinfunction "2_2") (pintype "passive"))
      (node (ref "C27") (pin "2") (pinfunction "2_2") (pintype "passive"))
      (node (ref "C28") (pin "2") (pinfunction "2_2") (pintype "passive"))
      (node (ref "C29") (pin "2") (pinfunction "2_2") (pintype "passive"))
      (node (ref "C30") (pin "2") (pinfunction "2_2") (pintype "passive"))
      (node (ref "L4") (pin "2") (pinfunction "2_2") (pintype "passive"))
      (node (ref "R4") (pin "1") (pinfunction "1_1") (pintype "passive"))
      (node (ref "R4") (pin "2") (pinfunction "2_2") (pintype "passive"))
      (node (ref "U1") (pin "37") (pinfunction "VOUT2_37") (pintype "passive"))
    )
    (net (code "46") (name "VDD_DDR_S0") (class "Default")
      (node (ref "C6") (pin "2") (pinfunction "2_2") (pintype "passive"))
      (node (ref "C7") (pin "2") (pinfunction "2_2") (pintype "passive"))
      (node (ref "C8") (pin "2") (pinfunction "2_2") (pintype "passive"))
      (node (ref "C9") (pin "1") (pinfunction "1_1") (pintype "passive"))
      (node (ref "C9") (pin "2") (pinfunction "2_2") (pintype "passive"))
      (node (ref "L1") (pin "2") (pinfunction "2_2") (pintype "passive"))
      (node (ref "R1") (pin "1") (pinfunction "1_1") (pintype "passive"))
      (node (ref "R1") (pin "2") (pinfunction "2_2") (pintype "passive"))
      (node (ref "U1") (pin "46") (pinfunction "VOUT5_46") (pintype "passive"))
    )
    (net (code "47") (name "VDD_GPU_S0") (class "Default")
      (node (ref "C10") (pin "1") (pinfunction "1_1") (pintype "passive"))
      (node (ref "C10") (pin "2") (pinfunction "2_2") (pintype "passive"))
      (node (ref "C11") (pin "2") (pinfunction "2_2") (pintype "passive"))
      (node (ref "C12") (pin "2") (pinfunction "2_2") (pintype "passive"))
      (node (ref "C13") (pin "2") (pinfunction "2_2") (pintype "passive"))
      (node (ref "C14") (pin "2") (pinfunction "2_2") (pintype "passive"))
      (node (ref "L2") (pin "2") (pinfunction "2_2") (pintype "passive"))
      (node (ref "R2") (pin "1") (pinfunction "1_1") (pintype "passive"))
      (node (ref "R2") (pin "2") (pinfunction "2_2") (pintype "passive"))
      (node (ref "U1") (pin "49") (pinfunction "VOUT1_49") (pintype "passive"))
    )
    (net (code "48") (name "VDD_LOGIC_S0") (class "Default")
      (node (ref "C43") (pin "1") (pinfunction "1_1") (pintype "passive"))
      (node (ref "C43") (pin "2") (pinfunction "2_2") (pintype "passive"))
      (node (ref "C44") (pin "2") (pinfunction "2_2") (pintype "passive"))
      (node (ref "C45") (pin "2") (pinfunction "2_2") (pintype "passive"))
      (node (ref "C46") (pin "2") (pinfunction "2_2") (pintype "passive"))
      (node (ref "C47") (pin "2") (pinfunction "2_2") (pintype "passive"))
      (node (ref "L6") (pin "2") (pinfunction "2_2") (pintype "passive"))
      (node (ref "R8") (pin "1") (pinfunction "1_1") (pintype "passive"))
      (node (ref "R8") (pin "2") (pinfunction "2_2") (pintype "passive"))
      (node (ref "U1") (pin "56") (pinfunction "VOUT3_56") (pintype "passive"))
    )
    (net (code "49") (name "VDD_VDENC_S0") (class "Default")
      (node (ref "C55") (pin "1") (pinfunction "1_1") (pintype "passive"))
      (node (ref "C55") (pin "2") (pinfunction "2_2") (pintype "passive"))
      (node (ref "C56") (pin "2") (pinfunction "2_2") (pintype "passive"))
      (node (ref "C57") (pin "2") (pinfunction "2_2") (pintype "passive"))
      (node (ref "C58") (pin "2") (pinfunction "2_2") (pintype "passive"))
      (node (ref "C59") (pin "2") (pinfunction "2_2") (pintype "passive"))
      (node (ref "L8") (pin "2") (pinfunction "2_2") (pintype "passive"))
      (node (ref "R10") (pin "1") (pinfunction "1_1") (pintype "passive"))
      (node (ref "R10") (pin "2") (pinfunction "2_2") (pintype "passive"))
      (node (ref "U1") (pin "24") (pinfunction "VOUT4_24") (pintype "passive"))
    )
    (net (code "50") (name "unconnected-(U1A-FB1-Pad48)") (class "Default")
      (node (ref "U1") (pin "48") (pinfunction "FB1_48") (pintype "passive+no_connect"))
    )
    (net (code "51") (name "unconnected-(U1A-FB2-Pad38)") (class "Default")
      (node (ref "U1") (pin "38") (pinfunction "FB2_38") (pintype "passive+no_connect"))
    )
    (net (code "52") (name "unconnected-(U1A-FB5-Pad47)") (class "Default")
      (node (ref "U1") (pin "47") (pinfunction "FB5_47") (pintype "passive+no_connect"))
    )
    (net (code "53") (name "unconnected-(U1C-SYNC-Pad2)") (class "Default")
      (node (ref "U1") (pin "2") (pinfunction "SYNC_2") (pintype "passive+no_connect"))
    )
    (net (code "54") (name "unconnected-(U1C-SYNC_CLK-Pad3)") (class "Default")
      (node (ref "U1") (pin "3") (pinfunction "SYNC_CLK_3") (pintype "passive+no_connect"))
    )
  )
)
